# top.net
KiCad netlist of a schematic drawn in Altium Designer
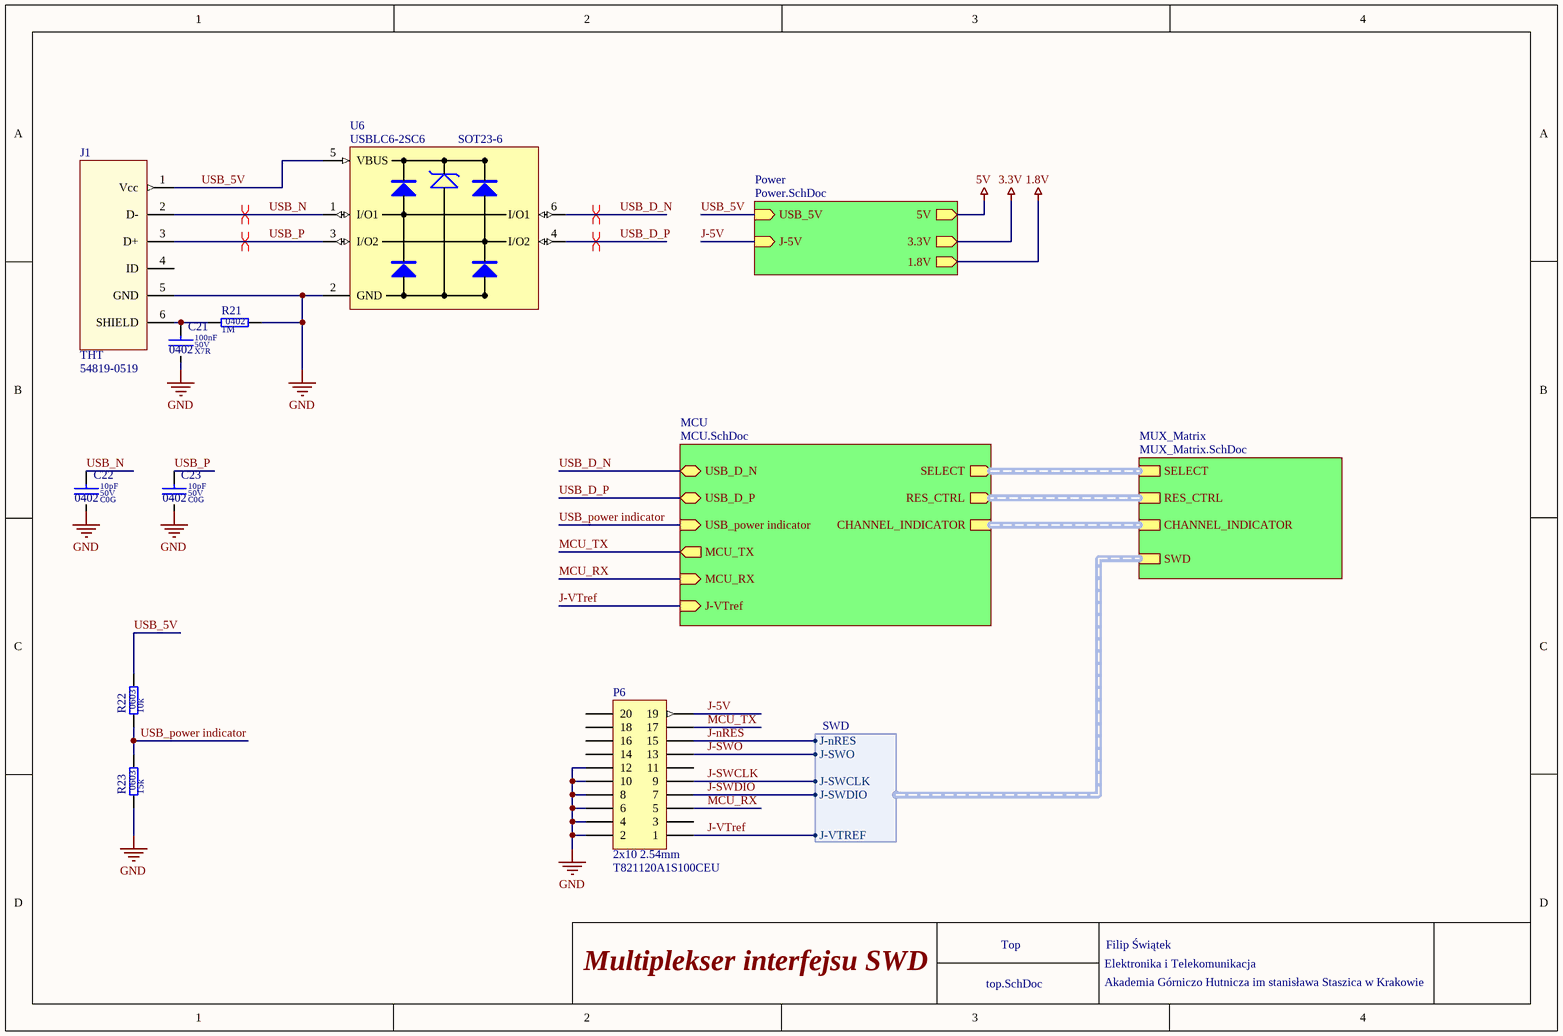
[diagram p0: top.SchDoc]

(export (version "E")
  (design (tool "Eeschema 10.0.6"))
  (components
    (comp (ref "C21")
      (value "100nF")
      (footprint "C_0402_1005")
      (description "Capacitor")
      (fields
        (field (name "DIELECTRIC") "X7R")
        (field (name "VOLTAGE") "50V")
        (field (name "SCH_FOOTPRINT") "0402")
        (field (name "PART NUMBER") "C_100nF_50V_X7R_0402_10")
        (field (name "MANUFACTURER") "Murata")
      )
      (libsource (lib "Library") (part "C"))
    )
    (comp (ref "C22")
      (value "10pF")
      (footprint "C_0402_1005")
      (description "Capacitor")
      (fields
        (field (name "DIELECTRIC") "C0G")
        (field (name "VOLTAGE") "50V")
        (field (name "SCH_FOOTPRINT") "0402")
        (field (name "PART NUMBER") "C_10pF_50V_C0G_0402_5")
        (field (name "MANUFACTURER") "Murata")
      )
      (libsource (lib "Library") (part "C"))
    )
    (comp (ref "C23")
      (value "10pF")
      (footprint "C_0402_1005")
      (description "Capacitor")
      (fields
        (field (name "DIELECTRIC") "C0G")
        (field (name "VOLTAGE") "50V")
        (field (name "SCH_FOOTPRINT") "0402")
        (field (name "PART NUMBER") "C_10pF_50V_C0G_0402_5")
        (field (name "MANUFACTURER") "Murata")
      )
      (libsource (lib "Library") (part "C"))
    )
    (comp (ref "J1")
      (value "54819-0519")
      (footprint "J_USB_MINIB_54819-0519_THT")
      (description "Złącze USB, Mini USB typu B, USB 2.0 OTG, Montaż przewlekany")
      (fields
        (field (name "PART NUMBER") "J_USB_MINIB_54819-0519")
        (field (name "SCH_FOOTPRINT") "THT")
        (field (name "MANUFACTURER") "Molex")
      )
      (libsource (lib "Library") (part "J_USB_MINIB_54819-0519_THT"))
    )
    (comp (ref "P6")
      (value "T821120A1S100CEU")
      (footprint "P_IDC_2x10_2.54")
      (description "Header, 20-Pin")
      (fields
        (field (name "SCH_FOOTPRINT") "2x10 2.54mm")
        (field (name "PART NUMBER") "P_IDC_2x10_2.54")
        (field (name "MANUFACTURER") "Amphenol")
      )
      (libsource (lib "Library") (part "P_HEADER_2x10"))
    )
    (comp (ref "R21")
      (value "1M")
      (footprint "R_0402_1005")
      (fields
        (field (name "SCH_FOOTPRINT") "0402")
        (field (name "PART NUMBER") "R_1M_0402_1")
        (field (name "VOLTAGE") "50V")
        (field (name "POWER") "200mW")
      )
      (libsource (lib "Library") (part "R"))
    )
    (comp (ref "R22")
      (value "10k")
      (footprint "R_0603_1608")
      (fields
        (field (name "SCH_FOOTPRINT") "0603")
        (field (name "PART NUMBER") "R_10k_0603_1")
        (field (name "VOLTAGE") "75V")
        (field (name "POWER") "100mW")
      )
      (libsource (lib "Library") (part "R"))
    )
    (comp (ref "R23")
      (value "15k")
      (footprint "R_0603_1608")
      (fields
        (field (name "SCH_FOOTPRINT") "0603")
        (field (name "PART NUMBER") "R_15k_0603_1")
        (field (name "VOLTAGE") "50V")
        (field (name "POWER") "100mW")
      )
      (libsource (lib "Library") (part "R"))
    )
    (comp (ref "U6")
      (value "USBLC6-2SC6")
      (footprint "SOT23-6_SC74A_SOT753")
      (description "USB 2.0/1.1, Ethernet and SIM card ESD protection")
      (fields
        (field (name "SCH_FOOTPRINT") "SOT23-6")
        (field (name "PART NUMBER") "U_USBLC6-2SC6")
        (field (name "MANUFACTURER") "STMicroelectronics")
      )
      (libsource (lib "Library") (part "U_USBLC6-2SC6"))
    )
  )
  (nets
    (net (code "3") (name "/J-5V") (class "Default")
      (node (ref "P6") (pin "19") (pinfunction "19_19") (pintype "output"))
    )
    (net (code "4") (name "/J-SWCLK") (class "Default")
      (node (ref "P6") (pin "9") (pinfunction "9_9") (pintype "passive"))
    )
    (net (code "5") (name "/J-SWDIO") (class "Default")
      (node (ref "P6") (pin "7") (pinfunction "7_7") (pintype "passive"))
    )
    (net (code "6") (name "/J-SWO") (class "Default")
      (node (ref "P6") (pin "13") (pinfunction "13_13") (pintype "passive"))
    )
    (net (code "7") (name "/J-VTref") (class "Default")
      (node (ref "P6") (pin "1") (pinfunction "1_1") (pintype "passive"))
    )
    (net (code "8") (name "/J-nRES") (class "Default")
      (node (ref "P6") (pin "15") (pinfunction "15_15") (pintype "passive"))
    )
    (net (code "9") (name "/MCU_RX") (class "Default")
      (node (ref "P6") (pin "5") (pinfunction "5_5") (pintype "passive"))
    )
    (net (code "10") (name "/MCU_TX") (class "Default")
      (node (ref "P6") (pin "17") (pinfunction "17_17") (pintype "passive"))
    )
    (net (code "13") (name "/USB_5V") (class "Default")
      (node (ref "J1") (pin "1") (pinfunction "Vcc_1") (pintype "output"))
      (node (ref "R22") (pin "2") (pinfunction "2_2") (pintype "passive"))
      (node (ref "U6") (pin "5") (pinfunction "VBUS_5") (pintype "input"))
    )
    (net (code "14") (name "/USB_D_N") (class "Default")
      (node (ref "U6") (pin "6") (pinfunction "I/O1_6") (pintype "bidirectional"))
    )
    (net (code "15") (name "/USB_D_P") (class "Default")
      (node (ref "U6") (pin "4") (pinfunction "I/O2_4") (pintype "bidirectional"))
    )
    (net (code "16") (name "/USB_N") (class "Default")
      (node (ref "C22") (pin "1") (pinfunction "1_1") (pintype "passive"))
      (node (ref "J1") (pin "2") (pinfunction "D-_2") (pintype "passive"))
      (node (ref "U6") (pin "1") (pinfunction "I/O1_1") (pintype "bidirectional"))
    )
    (net (code "17") (name "/USB_P") (class "Default")
      (node (ref "C23") (pin "1") (pinfunction "1_1") (pintype "passive"))
      (node (ref "J1") (pin "3") (pinfunction "D+_3") (pintype "passive"))
      (node (ref "U6") (pin "3") (pinfunction "I/O2_3") (pintype "bidirectional"))
    )
    (net (code "18") (name "/USB_power indicator") (class "Default")
      (node (ref "R22") (pin "1") (pinfunction "1_1") (pintype "passive"))
      (node (ref "R23") (pin "2") (pinfunction "2_2") (pintype "passive"))
    )
    (net (code "23") (name "GND") (class "Default")
      (node (ref "C21") (pin "2") (pinfunction "2_2") (pintype "passive"))
      (node (ref "C22") (pin "2") (pinfunction "2_2") (pintype "passive"))
      (node (ref "C23") (pin "2") (pinfunction "2_2") (pintype "passive"))
      (node (ref "J1") (pin "5") (pinfunction "GND_5") (pintype "power_in"))
      (node (ref "P6") (pin "10") (pinfunction "10_10") (pintype "passive"))
      (node (ref "P6") (pin "12") (pinfunction "12_12") (pintype "passive"))
      (node (ref "P6") (pin "2") (pinfunction "2_2") (pintype "passive"))
      (node (ref "P6") (pin "4") (pinfunction "4_4") (pintype "passive"))
      (node (ref "P6") (pin "6") (pinfunction "6_6") (pintype "passive"))
      (node (ref "P6") (pin "8") (pinfunction "8_8") (pintype "passive"))
      (node (ref "R21") (pin "2") (pinfunction "2_2") (pintype "passive"))
      (node (ref "R23") (pin "1") (pinfunction "1_1") (pintype "passive"))
      (node (ref "U6") (pin "2") (pinfunction "GND_2") (pintype "power_in"))
    )
    (net (code "24") (name "Net-(J1-SHIELD)") (class "Default")
      (node (ref "C21") (pin "1") (pinfunction "1_1") (pintype "passive"))
      (node (ref "J1") (pin "6") (pinfunction "SHIELD_6") (pintype "passive"))
      (node (ref "R21") (pin "1") (pinfunction "1_1") (pintype "passive"))
    )
    (net (code "25") (name "unconnected-(J1-ID-Pad4)") (class "Default")
      (node (ref "J1") (pin "4") (pinfunction "ID_4") (pintype "passive"))
    )
    (net (code "26") (name "unconnected-(P6-Pad3)") (class "Default")
      (node (ref "P6") (pin "3") (pinfunction "3_3") (pintype "passive"))
    )
    (net (code "27") (name "unconnected-(P6-Pad11)") (class "Default")
      (node (ref "P6") (pin "11") (pinfunction "11_11") (pintype "passive"))
    )
    (net (code "28") (name "unconnected-(P6-Pad14)") (class "Default")
      (node (ref "P6") (pin "14") (pinfunction "14_14") (pintype "passive"))
    )
    (net (code "29") (name "unconnected-(P6-Pad16)") (class "Default")
      (node (ref "P6") (pin "16") (pinfunction "16_16") (pintype "passive"))
    )
    (net (code "30") (name "unconnected-(P6-Pad18)") (class "Default")
      (node (ref "P6") (pin "18") (pinfunction "18_18") (pintype "passive"))
    )
    (net (code "31") (name "unconnected-(P6-Pad20)") (class "Default")
      (node (ref "P6") (pin "20") (pinfunction "20_20") (pintype "passive"))
    )
  )
)
